# Sheet3.net
KiCad netlist of a schematic drawn in Altium Designer
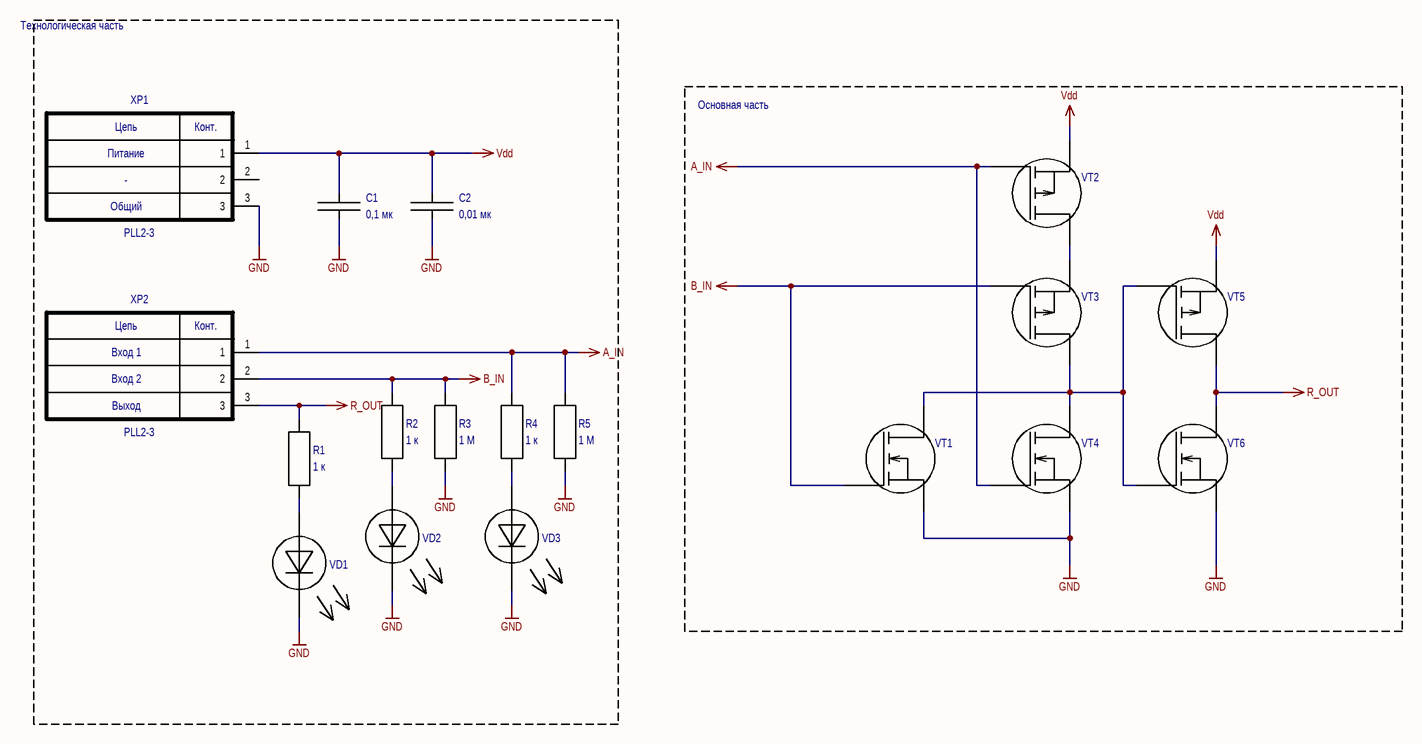
[diagram p0: Sheet3.SchDoc]

(export (version "E")
  (design (tool "Eeschema 10.0.6"))
  (components
    (comp (ref "C1")
      (value "0,1 мк")
      (footprint "K10-79_1.6_0.8(0603)")
      (fields
        (field (name "PARTNUMBER") "CC0603JRX7R8BB104")
        (field (name "TOLERANCE") "5 %")
        (field (name "Comment") "0,1 мкФ ±5 % *  0603, CC0603JRX7R8BB104")
      )
      (libsource (lib "components") (part "C - Конденсатор"))
    )
    (comp (ref "C2")
      (value "0,01 мк")
      (footprint "K10-79_1.6_0.8(0603)")
      (fields
        (field (name "PARTNUMBER") "CC0603KPX7R8BB103")
        (field (name "TOLERANCE") "10 %")
        (field (name "Comment") "0,01 мкФ ±10 % *  0603, CC0603KPX7R8BB103")
      )
      (libsource (lib "components") (part "C - Конденсатор"))
    )
    (comp (ref "R1")
      (value "1 к")
      (footprint "OR:P1-12-0.1(0603)")
      (fields
        (field (name "PARTNUMBER") "RC0603JR-071KL")
        (field (name "TOLERANCE") "5 %")
        (field (name "Comment") "1 кОм ±5 % 0603, RC0603JR-071KL")
      )
      (libsource (lib "components") (part "R - Резистор"))
    )
    (comp (ref "R2")
      (value "1 к")
      (footprint "OR:P1-12-0.1(0603)")
      (fields
        (field (name "PARTNUMBER") "RC0603JR-071KL")
        (field (name "TOLERANCE") "5 %")
        (field (name "Comment") "1 кОм ±5 % 0603, RC0603JR-071KL")
      )
      (libsource (lib "components") (part "R - Резистор"))
    )
    (comp (ref "R3")
      (value "1 М")
      (footprint "OR:P1-12-0.1(0603)")
      (fields
        (field (name "PARTNUMBER") "RC0603JR-071KL")
        (field (name "TOLERANCE") "5 %")
        (field (name "Comment") "1 МОм ±5 % 0603, RC0603JR-071KL")
      )
      (libsource (lib "components") (part "R - Резистор"))
    )
    (comp (ref "R4")
      (value "1 к")
      (footprint "OR:P1-12-0.1(0603)")
      (fields
        (field (name "PARTNUMBER") "RC0603JR-071KL")
        (field (name "TOLERANCE") "5 %")
        (field (name "Comment") "1 кОм ±5 % 0603, RC0603JR-071KL")
      )
      (libsource (lib "components") (part "R - Резистор"))
    )
    (comp (ref "R5")
      (value "1 М")
      (footprint "OR:P1-12-0.1(0603)")
      (fields
        (field (name "PARTNUMBER") "RC0603JR-071KL")
        (field (name "TOLERANCE") "5 %")
        (field (name "Comment") "1 МОм ±5 % 0603, RC0603JR-071KL")
      )
      (libsource (lib "components") (part "R - Резистор"))
    )
    (comp (ref "VD1")
      (value "VD - Светодиод")
      (footprint "LED 0603")
      (fields (field (name "PARTNUMBER") "GNL-0805UBC-TL"))
      (libsource (lib "components") (part "VD - Светодиод"))
    )
    (comp (ref "VD2")
      (value "VD - Светодиод")
      (footprint "LED 0603")
      (fields (field (name "PARTNUMBER") "GNL-0805UBC-TL"))
      (libsource (lib "components") (part "VD - Светодиод"))
    )
    (comp (ref "VD3")
      (value "VD - Светодиод")
      (footprint "LED 0603")
      (fields (field (name "PARTNUMBER") "GNL-0805UBC-TL"))
      (libsource (lib "components") (part "VD - Светодиод"))
    )
    (comp (ref "VT1")
      (value "VT - Полевой транзистор N канал (MOSFET_N)")
      (footprint "SOT23(KT-46)")
      (description "VT")
      (libsource (lib "ALU") (part "VT - Полевой транзистор N канал (MOSFET_N)"))
    )
    (comp (ref "VT2")
      (value "VT - Полевой транзистор P канал (MOSFET_P)")
      (footprint "SOT23(KT-46)")
      (description "VT")
      (libsource (lib "ALU") (part "VT - Полевой транзистор P канал (MOSFET_P)"))
    )
    (comp (ref "VT3")
      (value "VT - Полевой транзистор P канал (MOSFET_P)")
      (footprint "SOT23(KT-46)")
      (description "VT")
      (libsource (lib "ALU") (part "VT - Полевой транзистор P канал (MOSFET_P)"))
    )
    (comp (ref "VT4")
      (value "VT - Полевой транзистор N канал (MOSFET_N)")
      (footprint "SOT23(KT-46)")
      (description "VT")
      (libsource (lib "ALU") (part "VT - Полевой транзистор N канал (MOSFET_N)"))
    )
    (comp (ref "VT5")
      (value "VT - Полевой транзистор P канал (MOSFET_P)")
      (footprint "SOT23(KT-46)")
      (description "VT")
      (libsource (lib "ALU") (part "VT - Полевой транзистор P канал (MOSFET_P)"))
    )
    (comp (ref "VT6")
      (value "VT - Полевой транзистор N канал (MOSFET_N)")
      (footprint "SOT23(KT-46)")
      (description "VT")
      (libsource (lib "ALU") (part "VT - Полевой транзистор N канал (MOSFET_N)"))
    )
    (comp (ref "XP1")
      (value "Вилка PLL1.27-1x3 RUICHI")
      (footprint "OR:PCBComponent_1")
      (fields
        (field (name "1") "Питание")
        (field (name "3") "Общий")
        (field (name "2") "-")
        (field (name "PARTNUMBER") "PLL2-3")
      )
      (libsource (lib "components") (part "X - Контактное поле х3"))
    )
    (comp (ref "XP2")
      (value "KONT_POLE_POWER")
      (footprint "PCBComponent_1")
      (fields
        (field (name "1") "Вход 1")
        (field (name "2") "Вход 2")
        (field (name "3") "Выход")
        (field (name "PARTNUMBER") "PLL2-3")
      )
      (libsource (lib "components") (part "X - Контактное поле х3"))
    )
  )
  (nets
    (net (code "1") (name "A_IN") (class "Default")
      (node (ref "R4") (pin "1") (pinfunction "1_1") (pintype "passive"))
      (node (ref "R5") (pin "1") (pinfunction "1_1") (pintype "passive"))
      (node (ref "VT2") (pin "3") (pintype "passive"))
      (node (ref "VT4") (pin "3") (pintype "passive"))
      (node (ref "XP2") (pin "1") (pinfunction "1_1") (pintype "passive"))
    )
    (net (code "2") (name "B_IN") (class "Default")
      (node (ref "R2") (pin "1") (pinfunction "1_1") (pintype "passive"))
      (node (ref "R3") (pin "1") (pinfunction "1_1") (pintype "passive"))
      (node (ref "VT1") (pin "3") (pintype "passive"))
      (node (ref "VT3") (pin "3") (pintype "passive"))
      (node (ref "XP2") (pin "2") (pinfunction "2_2") (pintype "passive"))
    )
    (net (code "3") (name "GND") (class "Default")
      (node (ref "C1") (pin "1") (pinfunction "1_1") (pintype "passive"))
      (node (ref "C2") (pin "1") (pinfunction "1_1") (pintype "passive"))
      (node (ref "R3") (pin "2") (pinfunction "2_2") (pintype "passive"))
      (node (ref "R5") (pin "2") (pinfunction "2_2") (pintype "passive"))
      (node (ref "VD1") (pin "2") (pinfunction "C_2") (pintype "passive"))
      (node (ref "VD2") (pin "2") (pinfunction "C_2") (pintype "passive"))
      (node (ref "VD3") (pin "2") (pinfunction "C_2") (pintype "passive"))
      (node (ref "VT1") (pin "2") (pintype "passive"))
      (node (ref "VT4") (pin "2") (pintype "passive"))
      (node (ref "VT6") (pin "2") (pintype "passive"))
      (node (ref "XP1") (pin "3") (pinfunction "3_3") (pintype "passive"))
    )
    (net (code "4") (name "Net-(VD1-A)") (class "Default")
      (node (ref "R1") (pin "2") (pinfunction "2_2") (pintype "passive"))
      (node (ref "VD1") (pin "1") (pinfunction "A_1") (pintype "passive"))
    )
    (net (code "5") (name "Net-(VD2-A)") (class "Default")
      (node (ref "R2") (pin "2") (pinfunction "2_2") (pintype "passive"))
      (node (ref "VD2") (pin "1") (pinfunction "A_1") (pintype "passive"))
    )
    (net (code "6") (name "Net-(VD3-A)") (class "Default")
      (node (ref "R4") (pin "2") (pinfunction "2_2") (pintype "passive"))
      (node (ref "VD3") (pin "1") (pinfunction "A_1") (pintype "passive"))
    )
    (net (code "7") (name "Net-(VT1-Pad1)") (class "Default")
      (node (ref "VT1") (pin "1") (pintype "passive"))
      (node (ref "VT3") (pin "2") (pintype "passive"))
      (node (ref "VT4") (pin "1") (pintype "passive"))
      (node (ref "VT5") (pin "3") (pintype "passive"))
      (node (ref "VT6") (pin "3") (pintype "passive"))
    )
    (net (code "8") (name "Net-(VT2-Pad2)") (class "Default")
      (node (ref "VT2") (pin "2") (pintype "passive"))
      (node (ref "VT3") (pin "1") (pintype "passive"))
    )
    (net (code "9") (name "R_OUT") (class "Default")
      (node (ref "R1") (pin "1") (pinfunction "1_1") (pintype "passive"))
      (node (ref "VT5") (pin "2") (pintype "passive"))
      (node (ref "VT6") (pin "1") (pintype "passive"))
      (node (ref "XP2") (pin "3") (pinfunction "3_3") (pintype "passive"))
    )
    (net (code "10") (name "Vdd") (class "Default")
      (node (ref "C1") (pin "2") (pinfunction "2_2") (pintype "passive"))
      (node (ref "C2") (pin "2") (pinfunction "2_2") (pintype "passive"))
      (node (ref "VT2") (pin "1") (pintype "passive"))
      (node (ref "VT5") (pin "1") (pintype "passive"))
      (node (ref "XP1") (pin "1") (pinfunction "1_1") (pintype "passive"))
    )
    (net (code "11") (name "unconnected-(XP1-Pad2)") (class "Default")
      (node (ref "XP1") (pin "2") (pinfunction "2_2") (pintype "passive"))
    )
  )
)
